# DAC_SET2.net
KiCad netlist of a schematic drawn in Altium Designer
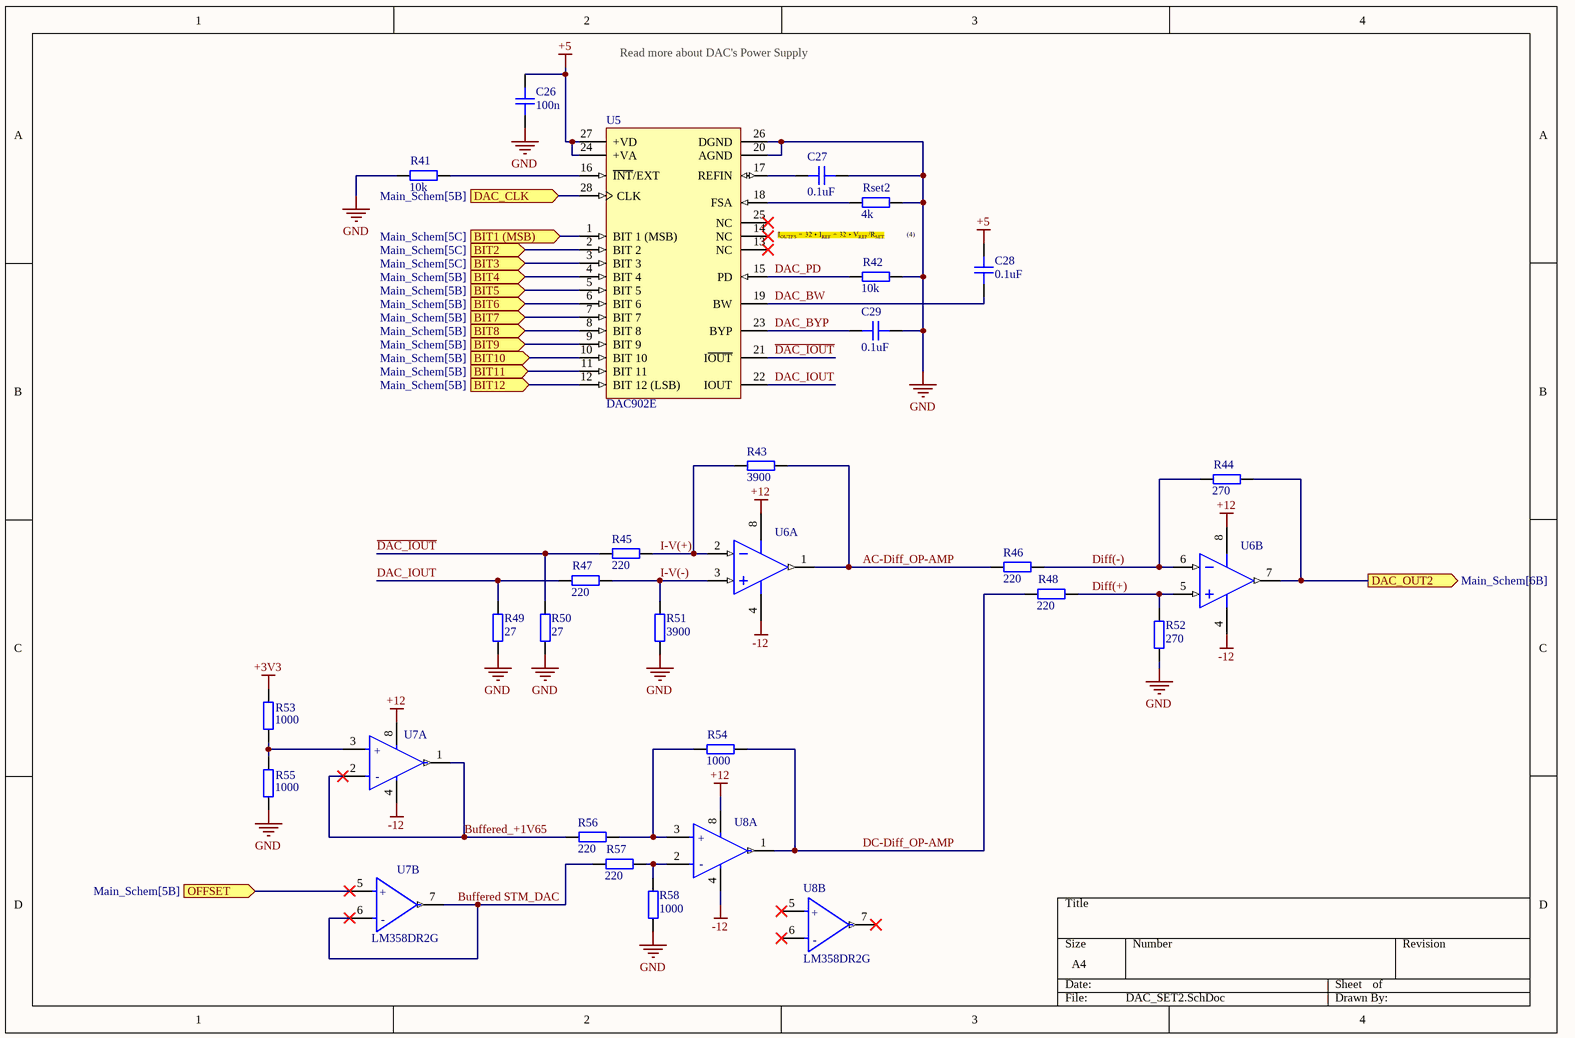
[diagram p0: DAC_SET2.SchDoc]

(export (version "E")
  (design (tool "Eeschema 10.0.6"))
  (components
    (comp (ref "C26")
      (value "100n")
      (footprint "CAP_0805")
      (description "Capacitor SMD 0805")
      (libsource (lib "Schematic-Lib-PhilsLab (1)") (part "CAP_0805"))
    )
    (comp (ref "C27")
      (value "0.1uF")
      (footprint "CAP_1210")
      (description "Capacitor SMD 1210")
      (libsource (lib "Schematic-Lib-PhilsLab (1)") (part "CAP_1210"))
    )
    (comp (ref "C28")
      (value "0.1uF")
      (footprint "CAP_1210")
      (description "Capacitor SMD 1210")
      (libsource (lib "Schematic-Lib-PhilsLab (1)") (part "CAP_1210"))
    )
    (comp (ref "C29")
      (value "0.1uF")
      (footprint "CAP_1210")
      (description "Capacitor SMD 1210")
      (libsource (lib "Schematic-Lib-PhilsLab (1)") (part "CAP_1210"))
    )
    (comp (ref "R41")
      (value "10k")
      (footprint "RES_0805")
      (description "Resistor SMD 0805")
      (libsource (lib "Schematic-Lib-PhilsLab (1)") (part "RES_0805"))
    )
    (comp (ref "R42")
      (value "10k")
      (footprint "RES_0805")
      (description "Resistor SMD 0805")
      (libsource (lib "Schematic-Lib-PhilsLab (1)") (part "RES_0805"))
    )
    (comp (ref "R43")
      (value "3900")
      (footprint "RES_0805")
      (description "Resistor SMD 0805")
      (libsource (lib "Schematic-Lib-PhilsLab (1)") (part "RES_0805"))
    )
    (comp (ref "R44")
      (value "270")
      (footprint "RES_0805")
      (description "Resistor SMD 0805")
      (libsource (lib "Schematic-Lib-PhilsLab (1)") (part "RES_0805"))
    )
    (comp (ref "R45")
      (value "220")
      (footprint "RES_0805")
      (description "Resistor SMD 0805")
      (libsource (lib "Schematic-Lib-PhilsLab (1)") (part "RES_0805"))
    )
    (comp (ref "R46")
      (value "220")
      (footprint "RES_0805")
      (description "Resistor SMD 0805")
      (libsource (lib "Schematic-Lib-PhilsLab (1)") (part "RES_0805"))
    )
    (comp (ref "R47")
      (value "220")
      (footprint "RES_0805")
      (description "Resistor SMD 0805")
      (libsource (lib "Schematic-Lib-PhilsLab (1)") (part "RES_0805"))
    )
    (comp (ref "R48")
      (value "220")
      (footprint "RES_0805")
      (description "Resistor SMD 0805")
      (libsource (lib "Schematic-Lib-PhilsLab (1)") (part "RES_0805"))
    )
    (comp (ref "R49")
      (value "27")
      (footprint "RES_0805")
      (description "Resistor SMD 0805")
      (libsource (lib "Schematic-Lib-PhilsLab (1)") (part "RES_0805"))
    )
    (comp (ref "R50")
      (value "27")
      (footprint "RES_0805")
      (description "Resistor SMD 0805")
      (libsource (lib "Schematic-Lib-PhilsLab (1)") (part "RES_0805"))
    )
    (comp (ref "R51")
      (value "3900")
      (footprint "RES_0805")
      (description "Resistor SMD 0805")
      (libsource (lib "Schematic-Lib-PhilsLab (1)") (part "RES_0805"))
    )
    (comp (ref "R52")
      (value "270")
      (footprint "RES_0805")
      (description "Resistor SMD 0805")
      (libsource (lib "Schematic-Lib-PhilsLab (1)") (part "RES_0805"))
    )
    (comp (ref "R53")
      (value "1000")
      (footprint "RES_0805")
      (description "Resistor SMD 0805")
      (libsource (lib "Schematic-Lib-PhilsLab (1)") (part "RES_0805"))
    )
    (comp (ref "R54")
      (value "1000")
      (footprint "RES_0805")
      (description "Resistor SMD 0805")
      (libsource (lib "Schematic-Lib-PhilsLab (1)") (part "RES_0805"))
    )
    (comp (ref "R55")
      (value "1000")
      (footprint "RES_0805")
      (description "Resistor SMD 0805")
      (libsource (lib "Schematic-Lib-PhilsLab (1)") (part "RES_0805"))
    )
    (comp (ref "R56")
      (value "220")
      (footprint "RES_0805")
      (description "Resistor SMD 0805")
      (libsource (lib "Schematic-Lib-PhilsLab (1)") (part "RES_0805"))
    )
    (comp (ref "R57")
      (value "220")
      (footprint "RES_0805")
      (description "Resistor SMD 0805")
      (libsource (lib "Schematic-Lib-PhilsLab (1)") (part "RES_0805"))
    )
    (comp (ref "R58")
      (value "1000")
      (footprint "RES_0805")
      (description "Resistor SMD 0805")
      (libsource (lib "Schematic-Lib-PhilsLab (1)") (part "RES_0805"))
    )
    (comp (ref "Rset2")
      (value "4k")
      (footprint "RES_0805")
      (description "Resistor SMD 0805")
      (libsource (lib "Schematic-Lib-PhilsLab (1)") (part "RES_0805"))
    )
    (comp (ref "U5")
      (value "DAC902E")
      (footprint "TI-PW28_L")
      (fields (field (name "MANUFACTURER") "Texas Instruments"))
      (libsource (lib "Altium Content Vault") (part "TI-DAC902-28"))
    )
    (comp (ref "U6")
      (value "AD8066ARZ-R7")
      (footprint "ADI-R-8_M")
      (fields (field (name "MANUFACTURER") "Analog Devices") (field (name "GENERIC PART NUMBER") "AD8066"))
      (libsource (lib "Altium Content Vault") (part "ADI-AD80XX-RX-8"))
    )
    (comp (ref "U7")
      (value "LM358DR2G")
      (footprint "FP-751-07-IPC_C")
      (description "IC OPAMP GP 2 CIRCUIT 8SOIC")
      (libsource (lib "Altium Content Vault") (part "992a6607d1d88c80ee6b45e5ba6cb1b"))
    )
    (comp (ref "U8")
      (value "LM358DR2G")
      (footprint "FP-751-07-IPC_C")
      (description "IC OPAMP GP 2 CIRCUIT 8SOIC")
      (libsource (lib "Altium Content Vault") (part "992a6607d1d88c80ee6b45e5ba6cb1b"))
    )
  )
  (nets
    (net (code "1") (name "+3V3") (class "Default")
      (node (ref "R53") (pin "1") (pinfunction "1_1") (pintype "passive"))
    )
    (net (code "2") (name "+5") (class "Default")
      (node (ref "C26") (pin "2") (pinfunction "2_2") (pintype "passive"))
      (node (ref "C28") (pin "2") (pinfunction "2_2") (pintype "passive"))
      (node (ref "U5") (pin "24") (pinfunction "+VA_24") (pintype "power_in"))
      (node (ref "U5") (pin "27") (pinfunction "+VD_27") (pintype "power_in"))
    )
    (net (code "3") (name "+12") (class "Default")
      (node (ref "U6") (pin "8") (pinfunction "+VS_8") (pintype "power_in"))
      (node (ref "U7") (pin "8") (pinfunction "VCC_8") (pintype "power_in"))
      (node (ref "U8") (pin "8") (pinfunction "VCC_8") (pintype "power_in"))
    )
    (net (code "4") (name "-12") (class "Default")
      (node (ref "U6") (pin "4") (pinfunction "-VS_4") (pintype "power_in"))
      (node (ref "U7") (pin "4") (pinfunction "VEE/GND_4") (pintype "power_in"))
      (node (ref "U8") (pin "4") (pinfunction "VEE/GND_4") (pintype "power_in"))
    )
    (net (code "5") (name "/AC-Diff_OP-AMP") (class "Default")
      (node (ref "R43") (pin "2") (pinfunction "2_2") (pintype "passive"))
      (node (ref "R46") (pin "2") (pinfunction "2_2") (pintype "passive"))
      (node (ref "U6") (pin "1") (pinfunction "VOUT_1_1") (pintype "output"))
    )
    (net (code "6") (name "/BIT1 (MSB)") (class "Default")
      (node (ref "U5") (pin "1") (pinfunction "BIT_1_(MSB)_1") (pintype "input"))
    )
    (net (code "7") (name "/BIT2") (class "Default")
      (node (ref "U5") (pin "2") (pinfunction "BIT_2_2") (pintype "input"))
    )
    (net (code "8") (name "/BIT3") (class "Default")
      (node (ref "U5") (pin "3") (pinfunction "BIT_3_3") (pintype "input"))
    )
    (net (code "9") (name "/BIT4") (class "Default")
      (node (ref "U5") (pin "4") (pinfunction "BIT_4_4") (pintype "input"))
    )
    (net (code "10") (name "/BIT5") (class "Default")
      (node (ref "U5") (pin "5") (pinfunction "BIT_5_5") (pintype "input"))
    )
    (net (code "11") (name "/BIT6") (class "Default")
      (node (ref "U5") (pin "6") (pinfunction "BIT_6_6") (pintype "input"))
    )
    (net (code "12") (name "/BIT7") (class "Default")
      (node (ref "U5") (pin "7") (pinfunction "BIT_7_7") (pintype "input"))
    )
    (net (code "13") (name "/BIT8") (class "Default")
      (node (ref "U5") (pin "8") (pinfunction "BIT_8_8") (pintype "input"))
    )
    (net (code "14") (name "/BIT9") (class "Default")
      (node (ref "U5") (pin "9") (pinfunction "BIT_9_9") (pintype "input"))
    )
    (net (code "15") (name "/BIT10") (class "Default")
      (node (ref "U5") (pin "10") (pinfunction "BIT_10_10") (pintype "input"))
    )
    (net (code "16") (name "/BIT11") (class "Default")
      (node (ref "U5") (pin "11") (pinfunction "BIT_11_11") (pintype "input"))
    )
    (net (code "17") (name "/BIT12") (class "Default")
      (node (ref "U5") (pin "12") (pinfunction "BIT_12_(LSB)_12") (pintype "input"))
    )
    (net (code "18") (name "/Buffered STM_DAC") (class "Default")
      (node (ref "R57") (pin "2") (pinfunction "2_2") (pintype "passive"))
      (node (ref "U7") (pin "6") (pinfunction "INPUT_B-_6") (pintype "tri_state"))
      (node (ref "U7") (pin "7") (pinfunction "OUTPUT_B_7") (pintype "output"))
    )
    (net (code "19") (name "/Buffered_+1V65") (class "Default")
      (node (ref "R56") (pin "2") (pinfunction "2_2") (pintype "passive"))
      (node (ref "U7") (pin "1") (pinfunction "OUTPUT_A_1") (pintype "output"))
      (node (ref "U7") (pin "2") (pinfunction "INPUT_A-_2") (pintype "tri_state"))
    )
    (net (code "20") (name "/DAC_BW") (class "Default")
      (node (ref "C28") (pin "1") (pinfunction "1_1") (pintype "passive"))
      (node (ref "U5") (pin "19") (pinfunction "BW_19") (pintype "passive"))
    )
    (net (code "21") (name "/DAC_BYP") (class "Default")
      (node (ref "C29") (pin "1") (pinfunction "1_1") (pintype "passive"))
      (node (ref "U5") (pin "23") (pinfunction "BYP_23") (pintype "passive"))
    )
    (net (code "22") (name "/DAC_CLK") (class "Default")
      (node (ref "U5") (pin "28") (pinfunction "CLK_28") (pintype "input"))
    )
    (net (code "23") (name "/DAC_IOUT") (class "Default")
      (node (ref "R47") (pin "2") (pinfunction "2_2") (pintype "passive"))
      (node (ref "R49") (pin "1") (pinfunction "1_1") (pintype "passive"))
      (node (ref "U5") (pin "22") (pinfunction "IOUT_22") (pintype "tri_state"))
    )
    (net (code "24") (name "/DAC_OUT2") (class "Default")
      (node (ref "R44") (pin "1") (pinfunction "1_1") (pintype "passive"))
      (node (ref "U6") (pin "7") (pinfunction "VOUT_2_7") (pintype "output"))
    )
    (net (code "25") (name "/DAC_PD") (class "Default")
      (node (ref "R42") (pin "2") (pinfunction "2_2") (pintype "passive"))
      (node (ref "U5") (pin "15") (pinfunction "PD_15") (pintype "input"))
    )
    (net (code "26") (name "/DC-Diff_OP-AMP") (class "Default")
      (node (ref "R48") (pin "2") (pinfunction "2_2") (pintype "passive"))
      (node (ref "R54") (pin "1") (pinfunction "1_1") (pintype "passive"))
      (node (ref "U8") (pin "1") (pinfunction "OUTPUT_A_1") (pintype "output"))
    )
    (net (code "27") (name "/Diff(+)") (class "Default")
      (node (ref "R48") (pin "1") (pinfunction "1_1") (pintype "passive"))
      (node (ref "R52") (pin "1") (pinfunction "1_1") (pintype "passive"))
      (node (ref "U6") (pin "5") (pinfunction "+IN_2_5") (pintype "input"))
    )
    (net (code "28") (name "/Diff(-)") (class "Default")
      (node (ref "R44") (pin "2") (pinfunction "2_2") (pintype "passive"))
      (node (ref "R46") (pin "1") (pinfunction "1_1") (pintype "passive"))
      (node (ref "U6") (pin "6") (pinfunction "-IN_2_6") (pintype "input"))
    )
    (net (code "29") (name "/I-V(+)") (class "Default")
      (node (ref "R43") (pin "1") (pinfunction "1_1") (pintype "passive"))
      (node (ref "R45") (pin "1") (pinfunction "1_1") (pintype "passive"))
      (node (ref "U6") (pin "2") (pinfunction "-IN_1_2") (pintype "input"))
    )
    (net (code "30") (name "/I-V(-)") (class "Default")
      (node (ref "R47") (pin "1") (pinfunction "1_1") (pintype "passive"))
      (node (ref "R51") (pin "1") (pinfunction "1_1") (pintype "passive"))
      (node (ref "U6") (pin "3") (pinfunction "+IN_1_3") (pintype "input"))
    )
    (net (code "31") (name "/OFFSET") (class "Default")
      (node (ref "U7") (pin "5") (pinfunction "INPUT_B+_5") (pintype "tri_state+no_connect"))
    )
    (net (code "32") (name "/~{DAC_IOUT}") (class "Default")
      (node (ref "R45") (pin "2") (pinfunction "2_2") (pintype "passive"))
      (node (ref "R50") (pin "1") (pinfunction "1_1") (pintype "passive"))
      (node (ref "U5") (pin "21") (pinfunction "I~{OUT}_21") (pintype "tri_state"))
    )
    (net (code "33") (name "GND") (class "Default")
      (node (ref "C26") (pin "1") (pinfunction "1_1") (pintype "passive"))
      (node (ref "C27") (pin "2") (pinfunction "2_2") (pintype "passive"))
      (node (ref "C29") (pin "2") (pinfunction "2_2") (pintype "passive"))
      (node (ref "R41") (pin "2") (pinfunction "2_2") (pintype "passive"))
      (node (ref "R42") (pin "1") (pinfunction "1_1") (pintype "passive"))
      (node (ref "R49") (pin "2") (pinfunction "2_2") (pintype "passive"))
      (node (ref "R50") (pin "2") (pinfunction "2_2") (pintype "passive"))
      (node (ref "R51") (pin "2") (pinfunction "2_2") (pintype "passive"))
      (node (ref "R52") (pin "2") (pinfunction "2_2") (pintype "passive"))
      (node (ref "R55") (pin "2") (pinfunction "2_2") (pintype "passive"))
      (node (ref "R58") (pin "2") (pinfunction "2_2") (pintype "passive"))
      (node (ref "Rset2") (pin "1") (pinfunction "1_1") (pintype "passive"))
      (node (ref "U5") (pin "20") (pinfunction "AGND_20") (pintype "power_in"))
      (node (ref "U5") (pin "26") (pinfunction "DGND_26") (pintype "power_in"))
    )
    (net (code "34") (name "Net-(U5-FSA)") (class "Default")
      (node (ref "Rset2") (pin "2") (pinfunction "2_2") (pintype "passive"))
      (node (ref "U5") (pin "18") (pinfunction "FSA_18") (pintype "input"))
    )
    (net (code "35") (name "Net-(U5-REFIN)") (class "Default")
      (node (ref "C27") (pin "1") (pinfunction "1_1") (pintype "passive"))
      (node (ref "U5") (pin "17") (pinfunction "REFIN_17") (pintype "bidirectional"))
    )
    (net (code "36") (name "Net-(U5-~{INT}{slash}EXT)") (class "Default")
      (node (ref "R41") (pin "1") (pinfunction "1_1") (pintype "passive"))
      (node (ref "U5") (pin "16") (pinfunction "~{INT}/EXT_16") (pintype "input"))
    )
    (net (code "37") (name "Net-(U7A-INPUT_A+)") (class "Default")
      (node (ref "R53") (pin "2") (pinfunction "2_2") (pintype "passive"))
      (node (ref "R55") (pin "1") (pinfunction "1_1") (pintype "passive"))
      (node (ref "U7") (pin "3") (pinfunction "INPUT_A+_3") (pintype "tri_state"))
    )
    (net (code "38") (name "Net-(U8A-INPUT_A+)") (class "Default")
      (node (ref "R54") (pin "2") (pinfunction "2_2") (pintype "passive"))
      (node (ref "R56") (pin "1") (pinfunction "1_1") (pintype "passive"))
      (node (ref "U8") (pin "3") (pinfunction "INPUT_A+_3") (pintype "tri_state"))
    )
    (net (code "39") (name "Net-(U8A-INPUT_A-)") (class "Default")
      (node (ref "R57") (pin "1") (pinfunction "1_1") (pintype "passive"))
      (node (ref "R58") (pin "1") (pinfunction "1_1") (pintype "passive"))
      (node (ref "U8") (pin "2") (pinfunction "INPUT_A-_2") (pintype "tri_state"))
    )
    (net (code "40") (name "unconnected-(U5-NC-Pad13)") (class "Default")
      (node (ref "U5") (pin "13") (pinfunction "NC_13") (pintype "passive+no_connect"))
    )
    (net (code "41") (name "unconnected-(U5-NC-Pad14)") (class "Default")
      (node (ref "U5") (pin "14") (pinfunction "NC_14") (pintype "passive+no_connect"))
    )
    (net (code "42") (name "unconnected-(U5-NC-Pad25)") (class "Default")
      (node (ref "U5") (pin "25") (pinfunction "NC_25") (pintype "passive+no_connect"))
    )
    (net (code "43") (name "unconnected-(U8B-INPUT_B+-Pad5)") (class "Default")
      (node (ref "U8") (pin "5") (pinfunction "INPUT_B+_5") (pintype "tri_state+no_connect"))
    )
    (net (code "44") (name "unconnected-(U8B-INPUT_B--Pad6)") (class "Default")
      (node (ref "U8") (pin "6") (pinfunction "INPUT_B-_6") (pintype "tri_state+no_connect"))
    )
    (net (code "45") (name "unconnected-(U8B-OUTPUT_B-Pad7)") (class "Default")
      (node (ref "U8") (pin "7") (pinfunction "OUTPUT_B_7") (pintype "output+no_connect"))
    )
  )
)
